# Offset_V03_R00.net
KiCad netlist of a schematic drawn in Altium Designer
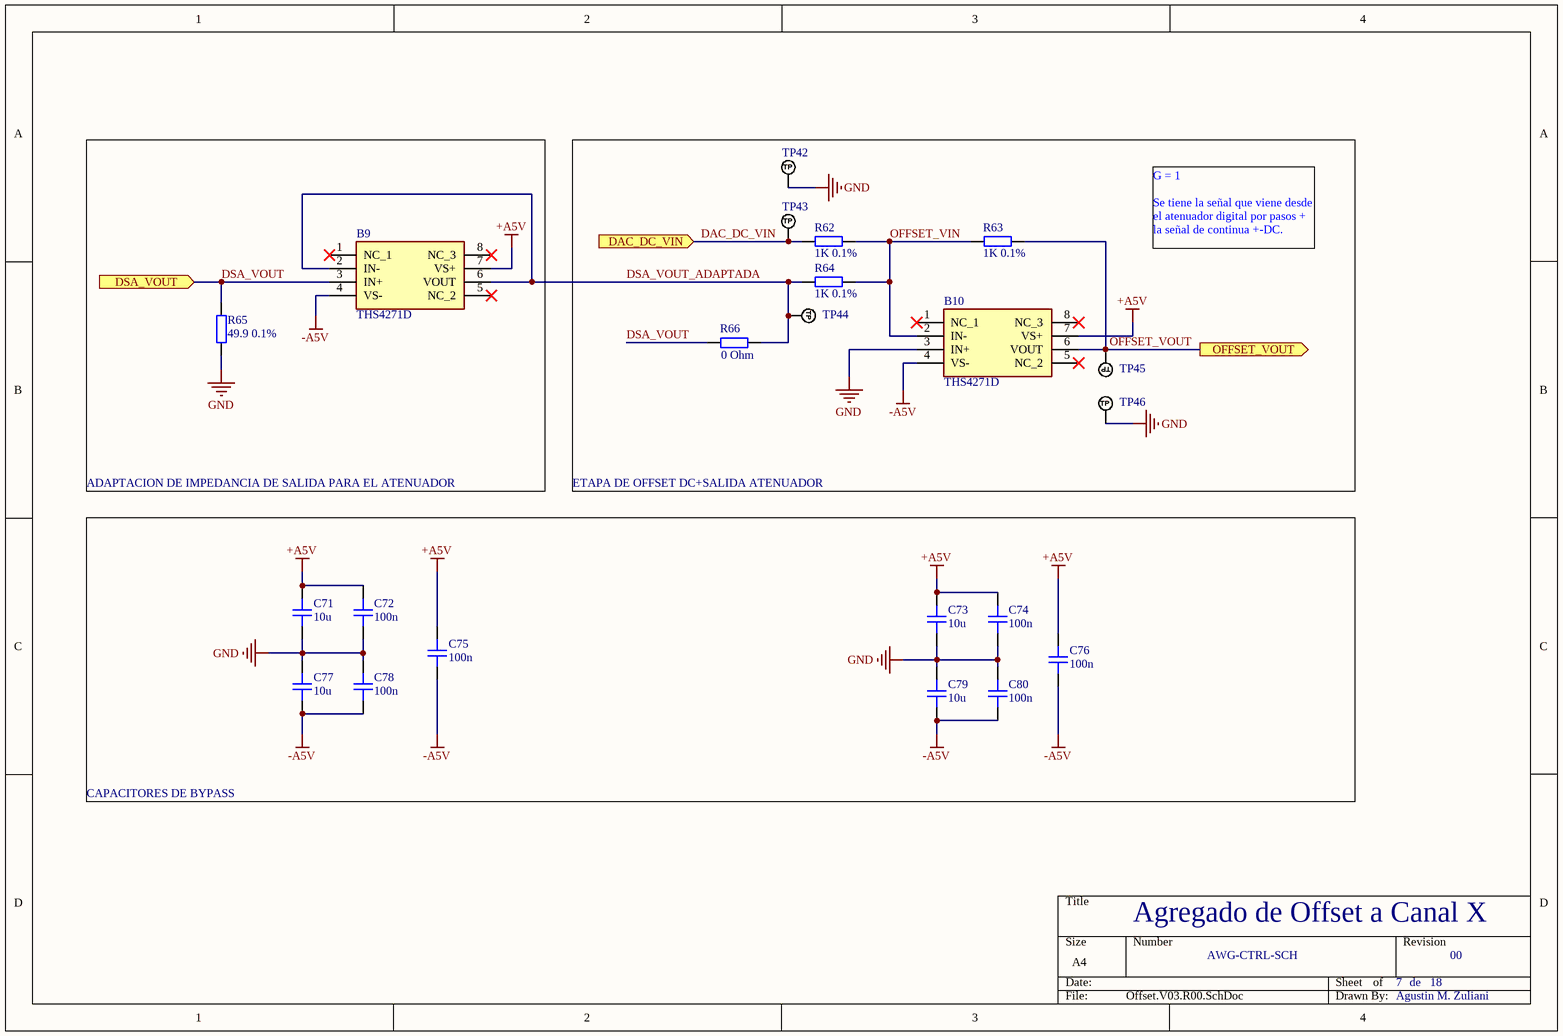
[diagram p0: Offset.V03.R00.SchDoc]

(export (version "E")
  (design (tool "Eeschema 10.0.6"))
  (components
    (comp (ref "B9")
      (value "THS4271D")
      (footprint "SOIC127P600X175-8N")
      (description "Super-Fast Ultra-Low Distortion High Speed Amplifier")
      (fields (field (name "MOUSER PART NUMBER") "595-THS4271D"))
      (libsource (lib "THS4271D") (part "THS4271D"))
    )
    (comp (ref "B10")
      (value "THS4271D")
      (footprint "SOIC127P600X175-8N")
      (description "Super-Fast Ultra-Low Distortion High Speed Amplifier")
      (fields (field (name "MOUSER PART NUMBER") "595-THS4271D"))
      (libsource (lib "THS4271D") (part "THS4271D"))
    )
    (comp (ref "C71")
      (value "10u")
      (footprint "CAP_0805")
      (description "Capacitor SMD 0805")
      (libsource (lib "Schematic-Lib-PhilsLab") (part "CAP_0805"))
    )
    (comp (ref "C72")
      (value "100n")
      (footprint "CAP_0805")
      (description "Capacitor SMD 0805")
      (libsource (lib "Schematic-Lib-PhilsLab") (part "CAP_0805"))
    )
    (comp (ref "C73")
      (value "10u")
      (footprint "CAP_0805")
      (description "Capacitor SMD 0805")
      (libsource (lib "Schematic-Lib-PhilsLab") (part "CAP_0805"))
    )
    (comp (ref "C74")
      (value "100n")
      (footprint "CAP_0805")
      (description "Capacitor SMD 0805")
      (libsource (lib "Schematic-Lib-PhilsLab") (part "CAP_0805"))
    )
    (comp (ref "C75")
      (value "100n")
      (footprint "CAP_0805")
      (description "Capacitor SMD 0805")
      (libsource (lib "Schematic-Lib-PhilsLab") (part "CAP_0805"))
    )
    (comp (ref "C76")
      (value "100n")
      (footprint "CAP_0805")
      (description "Capacitor SMD 0805")
      (libsource (lib "Schematic-Lib-PhilsLab") (part "CAP_0805"))
    )
    (comp (ref "C77")
      (value "10u")
      (footprint "CAP_0805")
      (description "Capacitor SMD 0805")
      (libsource (lib "Schematic-Lib-PhilsLab") (part "CAP_0805"))
    )
    (comp (ref "C78")
      (value "100n")
      (footprint "CAP_0805")
      (description "Capacitor SMD 0805")
      (libsource (lib "Schematic-Lib-PhilsLab") (part "CAP_0805"))
    )
    (comp (ref "C79")
      (value "10u")
      (footprint "CAP_0805")
      (description "Capacitor SMD 0805")
      (libsource (lib "Schematic-Lib-PhilsLab") (part "CAP_0805"))
    )
    (comp (ref "C80")
      (value "100n")
      (footprint "CAP_0805")
      (description "Capacitor SMD 0805")
      (libsource (lib "Schematic-Lib-PhilsLab") (part "CAP_0805"))
    )
    (comp (ref "R62")
      (value "1K 0.1%")
      (footprint "RES_0805")
      (description "Resistor SMD 0805")
      (libsource (lib "Schematic-Lib-PhilsLab") (part "RES_0805"))
    )
    (comp (ref "R63")
      (value "1K 0.1%")
      (footprint "RES_0805")
      (description "Resistor SMD 0805")
      (libsource (lib "Schematic-Lib-PhilsLab") (part "RES_0805"))
    )
    (comp (ref "R64")
      (value "1K 0.1%")
      (footprint "RES_0805")
      (description "Resistor SMD 0805")
      (libsource (lib "Schematic-Lib-PhilsLab") (part "RES_0805"))
    )
    (comp (ref "R65")
      (value "49.9 0.1%")
      (footprint "RES_0805")
      (description "Resistor SMD 0805")
      (libsource (lib "Schematic-Lib-PhilsLab") (part "RES_0805"))
    )
    (comp (ref "R66")
      (value "0 Ohm")
      (footprint "RES_0805")
      (description "Resistor SMD 0805")
      (libsource (lib "Schematic-Lib-PhilsLab") (part "RES_0805"))
    )
    (comp (ref "TP42")
      (value "TP_NOBOM")
      (footprint "PAD_RND_1MM")
      (description "Test Point Round 1mm (NO BOM)")
      (libsource (lib "Schematic-Lib-PhilsLab") (part "TEST_POINT_RND_1MM"))
    )
    (comp (ref "TP43")
      (value "TP_NOBOM")
      (footprint "PAD_RND_1MM")
      (description "Test Point Round 1mm (NO BOM)")
      (libsource (lib "Schematic-Lib-PhilsLab") (part "TEST_POINT_RND_1MM"))
    )
    (comp (ref "TP44")
      (value "TP_NOBOM")
      (footprint "PAD_RND_1MM")
      (description "Test Point Round 1mm (NO BOM)")
      (libsource (lib "Schematic-Lib-PhilsLab") (part "TEST_POINT_RND_1MM"))
    )
    (comp (ref "TP45")
      (value "TP_NOBOM")
      (footprint "PAD_RND_1MM")
      (description "Test Point Round 1mm (NO BOM)")
      (libsource (lib "Schematic-Lib-PhilsLab") (part "TEST_POINT_RND_1MM"))
    )
    (comp (ref "TP46")
      (value "TP_NOBOM")
      (footprint "PAD_RND_1MM")
      (description "Test Point Round 1mm (NO BOM)")
      (libsource (lib "Schematic-Lib-PhilsLab") (part "TEST_POINT_RND_1MM"))
    )
  )
  (nets
    (net (code "1") (name "+A5V") (class "Default")
      (node (ref "B10") (pin "7") (pinfunction "VS+_7") (pintype "passive"))
      (node (ref "B9") (pin "7") (pinfunction "VS+_7") (pintype "passive"))
      (node (ref "C71") (pin "2") (pinfunction "2_2") (pintype "passive"))
      (node (ref "C72") (pin "2") (pinfunction "2_2") (pintype "passive"))
      (node (ref "C73") (pin "2") (pinfunction "2_2") (pintype "passive"))
      (node (ref "C74") (pin "2") (pinfunction "2_2") (pintype "passive"))
      (node (ref "C75") (pin "2") (pinfunction "2_2") (pintype "passive"))
      (node (ref "C76") (pin "2") (pinfunction "2_2") (pintype "passive"))
    )
    (net (code "2") (name "-A5V") (class "Default")
      (node (ref "B10") (pin "4") (pinfunction "VS-_4") (pintype "passive"))
      (node (ref "B9") (pin "4") (pinfunction "VS-_4") (pintype "passive"))
      (node (ref "C75") (pin "1") (pinfunction "1_1") (pintype "passive"))
      (node (ref "C76") (pin "1") (pinfunction "1_1") (pintype "passive"))
      (node (ref "C77") (pin "1") (pinfunction "1_1") (pintype "passive"))
      (node (ref "C78") (pin "1") (pinfunction "1_1") (pintype "passive"))
      (node (ref "C79") (pin "1") (pinfunction "1_1") (pintype "passive"))
      (node (ref "C80") (pin "1") (pinfunction "1_1") (pintype "passive"))
    )
    (net (code "3") (name "/DAC_DC_VIN") (class "Default")
      (node (ref "R62") (pin "1") (pinfunction "1_1") (pintype "passive"))
      (node (ref "TP43") (pin "1") (pinfunction "TP_1") (pintype "passive"))
    )
    (net (code "4") (name "/DSA_VOUT") (class "Default")
      (node (ref "B9") (pin "3") (pinfunction "IN+_3") (pintype "passive"))
      (node (ref "R65") (pin "2") (pinfunction "2_2") (pintype "passive"))
      (node (ref "R66") (pin "1") (pinfunction "1_1") (pintype "passive"))
    )
    (net (code "5") (name "/DSA_VOUT_ADAPTADA") (class "Default")
      (node (ref "B9") (pin "2") (pinfunction "IN-_2") (pintype "passive"))
      (node (ref "B9") (pin "6") (pinfunction "VOUT_6") (pintype "passive"))
      (node (ref "R64") (pin "1") (pinfunction "1_1") (pintype "passive"))
      (node (ref "R66") (pin "2") (pinfunction "2_2") (pintype "passive"))
      (node (ref "TP44") (pin "1") (pinfunction "TP_1") (pintype "passive"))
    )
    (net (code "6") (name "/OFFSET_VIN") (class "Default")
      (node (ref "B10") (pin "2") (pinfunction "IN-_2") (pintype "passive"))
      (node (ref "R62") (pin "2") (pinfunction "2_2") (pintype "passive"))
      (node (ref "R63") (pin "1") (pinfunction "1_1") (pintype "passive"))
      (node (ref "R64") (pin "2") (pinfunction "2_2") (pintype "passive"))
    )
    (net (code "7") (name "/OFFSET_VOUT") (class "Default")
      (node (ref "B10") (pin "6") (pinfunction "VOUT_6") (pintype "passive"))
      (node (ref "R63") (pin "2") (pinfunction "2_2") (pintype "passive"))
      (node (ref "TP45") (pin "1") (pinfunction "TP_1") (pintype "passive"))
    )
    (net (code "8") (name "GND") (class "Default")
      (node (ref "B10") (pin "3") (pinfunction "IN+_3") (pintype "passive"))
      (node (ref "C71") (pin "1") (pinfunction "1_1") (pintype "passive"))
      (node (ref "C72") (pin "1") (pinfunction "1_1") (pintype "passive"))
      (node (ref "C73") (pin "1") (pinfunction "1_1") (pintype "passive"))
      (node (ref "C74") (pin "1") (pinfunction "1_1") (pintype "passive"))
      (node (ref "C77") (pin "2") (pinfunction "2_2") (pintype "passive"))
      (node (ref "C78") (pin "2") (pinfunction "2_2") (pintype "passive"))
      (node (ref "C79") (pin "2") (pinfunction "2_2") (pintype "passive"))
      (node (ref "C80") (pin "2") (pinfunction "2_2") (pintype "passive"))
      (node (ref "R65") (pin "1") (pinfunction "1_1") (pintype "passive"))
      (node (ref "TP42") (pin "1") (pinfunction "TP_1") (pintype "passive"))
      (node (ref "TP46") (pin "1") (pinfunction "TP_1") (pintype "passive"))
    )
    (net (code "9") (name "unconnected-(B9-NC_1-Pad1)") (class "Default")
      (node (ref "B9") (pin "1") (pinfunction "NC_1_1") (pintype "passive+no_connect"))
    )
    (net (code "10") (name "unconnected-(B9-NC_2-Pad5)") (class "Default")
      (node (ref "B9") (pin "5") (pinfunction "NC_2_5") (pintype "passive+no_connect"))
    )
    (net (code "11") (name "unconnected-(B9-NC_3-Pad8)") (class "Default")
      (node (ref "B9") (pin "8") (pinfunction "NC_3_8") (pintype "passive+no_connect"))
    )
    (net (code "12") (name "unconnected-(B10-NC_1-Pad1)") (class "Default")
      (node (ref "B10") (pin "1") (pinfunction "NC_1_1") (pintype "passive+no_connect"))
    )
    (net (code "13") (name "unconnected-(B10-NC_2-Pad5)") (class "Default")
      (node (ref "B10") (pin "5") (pinfunction "NC_2_5") (pintype "passive+no_connect"))
    )
    (net (code "14") (name "unconnected-(B10-NC_3-Pad8)") (class "Default")
      (node (ref "B10") (pin "8") (pinfunction "NC_3_8") (pintype "passive+no_connect"))
    )
  )
)
